# TOP.net
KiCad netlist of a schematic drawn in Altium Designer
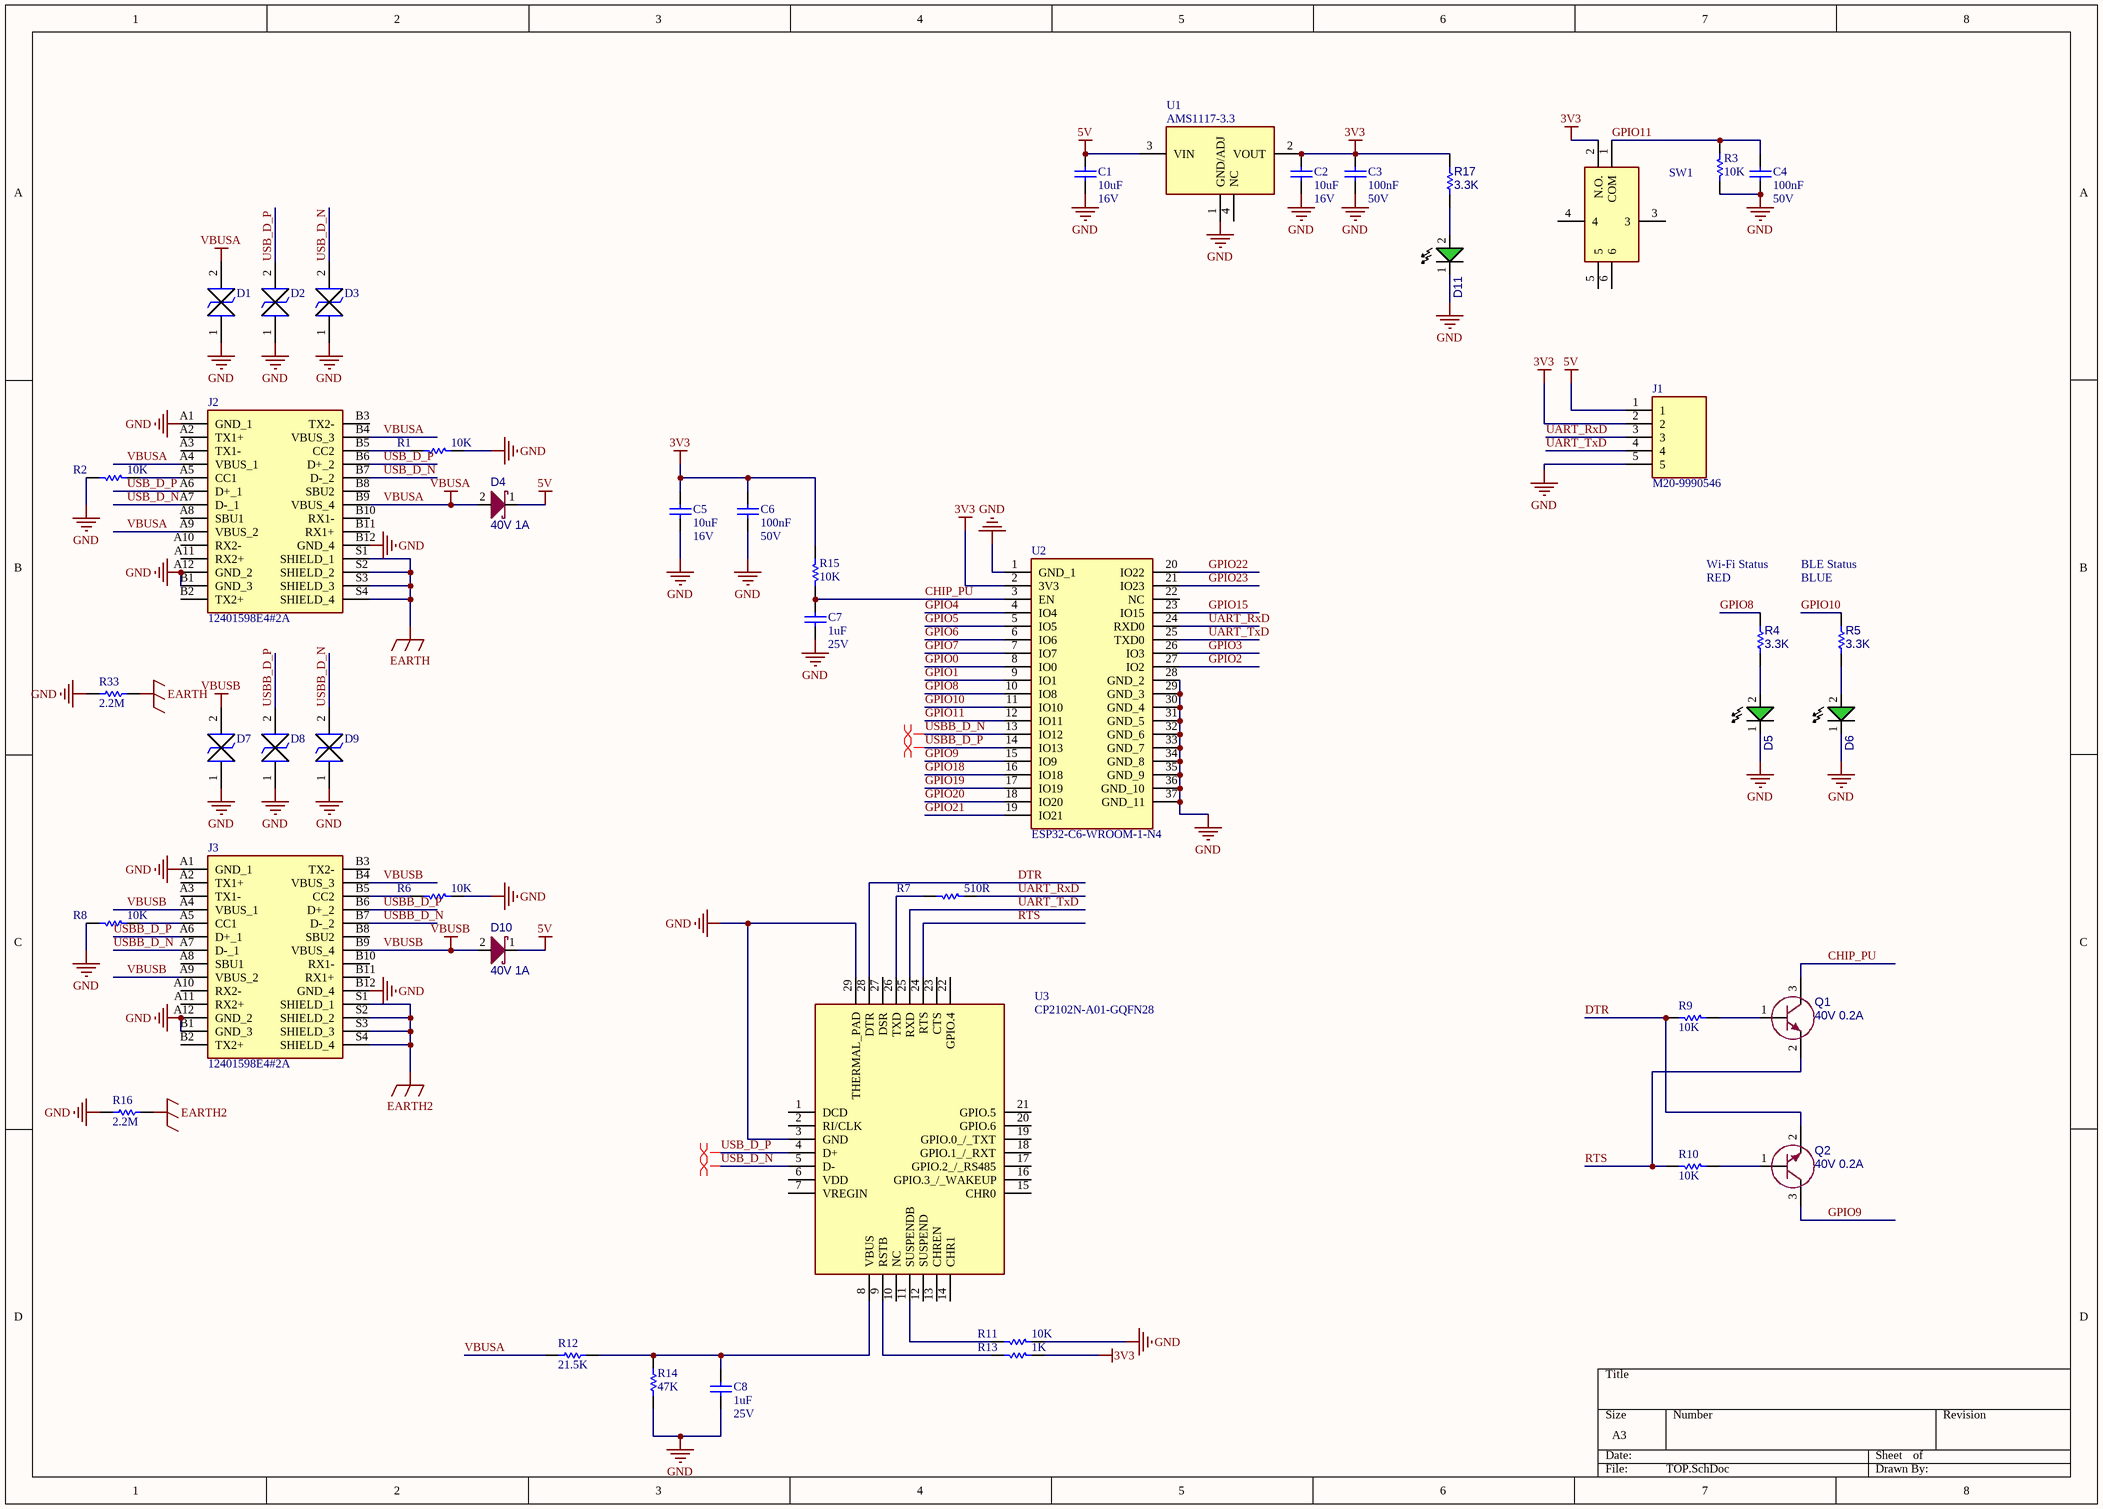
[diagram p0: TOP.SchDoc]

(export (version "E")
  (design (tool "Eeschema 10.0.6"))
  (components
    (comp (ref "C1")
      (value "10uF")
      (footprint "CAP_0805")
      (description "CAP CER 10UF 16VDC %10 X5R SMD")
      (fields
        (field (name "VOLTAGE") "16V")
        (field (name "MANUFACTURER") "Samsung")
        (field (name "MANUFACTURER PART NUMBER") "CL21A106KOQNNNE")
      )
      (libsource (lib "open-components") (part "CAP"))
    )
    (comp (ref "C2")
      (value "10uF")
      (footprint "CAP_0805")
      (description "CAP CER 10UF 16VDC %10 X5R SMD")
      (fields
        (field (name "VOLTAGE") "16V")
        (field (name "MANUFACTURER") "Samsung")
        (field (name "MANUFACTURER PART NUMBER") "CL21A106KOQNNNE")
      )
      (libsource (lib "open-components") (part "CAP"))
    )
    (comp (ref "C3")
      (value "100nF")
      (footprint "CAP_0603")
      (description "CAP CER 100nF 50VDC %10 X7R SMD")
      (fields
        (field (name "VOLTAGE") "50V")
        (field (name "MANUFACTURER") "Samsung")
        (field (name "MANUFACTURER PART NUMBER") "CL10B104KB8NNNL")
      )
      (libsource (lib "open-components") (part "CAP"))
    )
    (comp (ref "C4")
      (value "100nF")
      (footprint "CAP_0603")
      (description "CAP CER 100nF 50VDC %10 X7R SMD")
      (fields
        (field (name "VOLTAGE") "50V")
        (field (name "MANUFACTURER") "Samsung")
        (field (name "MANUFACTURER PART NUMBER") "CL10B104KB8NNNL")
      )
      (libsource (lib "open-components") (part "CAP"))
    )
    (comp (ref "C5")
      (value "10uF")
      (footprint "CAP_0805")
      (description "CAP CER 10UF 16VDC %10 X5R SMD")
      (fields
        (field (name "VOLTAGE") "16V")
        (field (name "MANUFACTURER") "Samsung")
        (field (name "MANUFACTURER PART NUMBER") "CL21A106KOQNNNE")
      )
      (libsource (lib "open-components") (part "CAP"))
    )
    (comp (ref "C6")
      (value "100nF")
      (footprint "CAP_0603")
      (description "CAP CER 100nF 50VDC %10 X7R SMD")
      (fields
        (field (name "VOLTAGE") "50V")
        (field (name "MANUFACTURER") "Samsung")
        (field (name "MANUFACTURER PART NUMBER") "CL10B104KB8NNNL")
      )
      (libsource (lib "open-components") (part "CAP"))
    )
    (comp (ref "C7")
      (value "1uF")
      (footprint "CAP_0603")
      (description "CAP CER 1UF 25VDC %10 X5R SMD")
      (fields
        (field (name "VOLTAGE") "25V")
        (field (name "MANUFACTURER") "Samsung")
        (field (name "MANUFACTURER PART NUMBER") "CL10A105KA8NNNC")
      )
      (libsource (lib "open-components") (part "CAP"))
    )
    (comp (ref "C8")
      (value "1uF")
      (footprint "CAP_0603")
      (description "CAP CER 1UF 25VDC %10 X5R SMD")
      (fields
        (field (name "VOLTAGE") "25V")
        (field (name "MANUFACTURER") "Samsung")
        (field (name "MANUFACTURER PART NUMBER") "CL10A105KA8NNNC")
      )
      (libsource (lib "open-components") (part "CAP"))
    )
    (comp (ref "D1")
      (value "ATV02W5V0B-HF")
      (footprint "SamacSys:SODFL3718X130N")
      (description "TVS Diode (Bi-directional)")
      (fields (field (name "MANUFACTURER") "Comchip Technology"))
      (libsource (lib "SamacSys") (part "ATV02W5V0B-HF"))
    )
    (comp (ref "D2")
      (value "ATV02W5V0B-HF")
      (footprint "SamacSys:SODFL3718X130N")
      (description "TVS Diode (Bi-directional)")
      (fields (field (name "MANUFACTURER") "Comchip Technology"))
      (libsource (lib "SamacSys") (part "ATV02W5V0B-HF"))
    )
    (comp (ref "D3")
      (value "ATV02W5V0B-HF")
      (footprint "SamacSys:SODFL3718X130N")
      (description "TVS Diode (Bi-directional)")
      (fields (field (name "MANUFACTURER") "Comchip Technology"))
      (libsource (lib "SamacSys") (part "ATV02W5V0B-HF"))
    )
    (comp (ref "D4")
      (value "40V 1A")
      (footprint "SOD-123")
      (description "DIODE SCHOTTKY 40V 1A SOD123")
      (fields
        (field (name "MANUFACTURER") "Nexperia USA Inc.")
        (field (name "MANUFACTURER PART NUMBER") "PMEG4010EGWJ")
      )
      (libsource (lib "Semiconductors") (part "PMEG4010EGWJ"))
    )
    (comp (ref "D5")
      (value "PSC-1608U52GC-G4")
      (footprint "LED_0603_GRN")
      (description "LED GREEN WATER CLEAR 0603 SMD")
      (fields (field (name "MANUFACTURER") "HONGLITRONIC"))
      (libsource (lib "Semiconductors") (part "LTST-C190TGKT"))
    )
    (comp (ref "D6")
      (value "PSC-1608U52GC-G4")
      (footprint "LED_0603_GRN")
      (description "LED GREEN WATER CLEAR 0603 SMD")
      (fields (field (name "MANUFACTURER") "HONGLITRONIC"))
      (libsource (lib "Semiconductors") (part "LTST-C190TGKT"))
    )
    (comp (ref "D7")
      (value "ATV02W5V0B-HF")
      (footprint "SamacSys:SODFL3718X130N")
      (description "TVS Diode (Bi-directional)")
      (fields (field (name "MANUFACTURER") "Comchip Technology"))
      (libsource (lib "SamacSys") (part "ATV02W5V0B-HF"))
    )
    (comp (ref "D8")
      (value "ATV02W5V0B-HF")
      (footprint "SamacSys:SODFL3718X130N")
      (description "TVS Diode (Bi-directional)")
      (fields (field (name "MANUFACTURER") "Comchip Technology"))
      (libsource (lib "SamacSys") (part "ATV02W5V0B-HF"))
    )
    (comp (ref "D9")
      (value "ATV02W5V0B-HF")
      (footprint "SamacSys:SODFL3718X130N")
      (description "TVS Diode (Bi-directional)")
      (fields (field (name "MANUFACTURER") "Comchip Technology"))
      (libsource (lib "SamacSys") (part "ATV02W5V0B-HF"))
    )
    (comp (ref "D10")
      (value "40V 1A")
      (footprint "SOD-123")
      (description "DIODE SCHOTTKY 40V 1A SOD123")
      (fields
        (field (name "MANUFACTURER") "Nexperia USA Inc.")
        (field (name "MANUFACTURER PART NUMBER") "PMEG4010EGWJ")
      )
      (libsource (lib "Semiconductors") (part "PMEG4010EGWJ"))
    )
    (comp (ref "D11")
      (value "PSC-1608U52GC-G4")
      (footprint "LED_0603_GRN")
      (description "LED GREEN WATER CLEAR 0603 SMD")
      (fields (field (name "MANUFACTURER") "HONGLITRONIC"))
      (libsource (lib "Semiconductors") (part "LTST-C190TGKT"))
    )
    (comp (ref "J1")
      (value "M20-9990546")
      (footprint "SamacSys:HDRV5W64P0X254_1X5_1270X254X864P")
      (description "Connector")
      (fields (field (name "MANUFACTURER") "Harwin"))
      (libsource (lib "*") (part "M20-9990546"))
    )
    (comp (ref "J2")
      (value "12401598E4#2A")
      (footprint "12401598E42A")
      (description "Connector")
      (fields (field (name "MANUFACTURER") "Amphenol"))
      (libsource (lib "*") (part "12401598E4#2A"))
    )
    (comp (ref "J3")
      (value "12401598E4#2A")
      (footprint "12401598E42A")
      (description "Connector")
      (fields (field (name "MANUFACTURER") "Amphenol"))
      (libsource (lib "*") (part "12401598E4#2A"))
    )
    (comp (ref "Q1")
      (value "40V 0.2A")
      (footprint "SOT23")
      (description "TRANSISTOR NPN 40V 0.2A SOT23-3")
      (fields
        (field (name "MANUFACTURER") "Diodes Incorporated")
        (field (name "MANUFACTURER PART NUMBER") "MMBT3904-7-F")
      )
      (libsource (lib "Semiconductors") (part "MMBT3904-7-F"))
    )
    (comp (ref "Q2")
      (value "40V 0.2A")
      (footprint "SOT23")
      (description "TRANSISTOR NPN 40V 0.2A SOT23-3")
      (fields
        (field (name "MANUFACTURER") "Diodes Incorporated")
        (field (name "MANUFACTURER PART NUMBER") "MMBT3904-7-F")
      )
      (libsource (lib "Semiconductors") (part "MMBT3904-7-F"))
    )
    (comp (ref "R1")
      (value "10K")
      (footprint "RES_0603")
      (description "RES 0603 10k Ohms %1 1/10W 100PPM")
      (fields
        (field (name "MANUFACTURER") "ROYALOHM")
        (field (name "MANUFACTURER PART NUMBER") "0603SAF1002T5E")
      )
      (libsource (lib "open-components") (part "RES"))
    )
    (comp (ref "R2")
      (value "10K")
      (footprint "RES_0603")
      (description "RES 0603 10k Ohms %1 1/10W 100PPM")
      (fields
        (field (name "MANUFACTURER") "ROYALOHM")
        (field (name "MANUFACTURER PART NUMBER") "0603SAF1002T5E")
      )
      (libsource (lib "open-components") (part "RES"))
    )
    (comp (ref "R3")
      (value "10K")
      (footprint "RES_0603")
      (description "RES 0603 10k Ohms %1 1/10W 100PPM")
      (fields
        (field (name "MANUFACTURER") "ROYALOHM")
        (field (name "MANUFACTURER PART NUMBER") "0603SAF1002T5E")
      )
      (libsource (lib "open-components") (part "RES"))
    )
    (comp (ref "R4")
      (value "3.3K")
      (footprint "RES_0603")
      (description "RES.(1608) 0603 3.3K Ohms 1% 1/10W 100PPM SMT")
      (fields
        (field (name "MANUFACTURER") "YAGEO")
        (field (name "MANUFACTURER PART NUMBER") "RC0603FR-073K74L")
      )
      (libsource (lib "Passives") (part "0603SAF3301T5E"))
    )
    (comp (ref "R5")
      (value "3.3K")
      (footprint "RES_0603")
      (description "RES.(1608) 0603 3.3K Ohms 1% 1/10W 100PPM SMT")
      (fields
        (field (name "MANUFACTURER") "YAGEO")
        (field (name "MANUFACTURER PART NUMBER") "RC0603FR-073K74L")
      )
      (libsource (lib "Passives") (part "0603SAF3301T5E"))
    )
    (comp (ref "R6")
      (value "10K")
      (footprint "RES_0603")
      (description "RES 0603 10k Ohms %1 1/10W 100PPM")
      (fields
        (field (name "MANUFACTURER") "ROYALOHM")
        (field (name "MANUFACTURER PART NUMBER") "0603SAF1002T5E")
      )
      (libsource (lib "open-components") (part "RES"))
    )
    (comp (ref "R7")
      (value "510R")
      (footprint "R0603")
      (description "RES.(1608) 0603 510 Ohms 5% 1/10W-S 100PPM")
      (fields
        (field (name "MANUFACTURER") "ROYALOHM")
        (field (name "MANUFACTURER PART NUMBER") "0603SAJ0511T5E")
      )
      (libsource (lib "open-components") (part "RES"))
    )
    (comp (ref "R8")
      (value "10K")
      (footprint "RES_0603")
      (description "RES 0603 10k Ohms %1 1/10W 100PPM")
      (fields
        (field (name "MANUFACTURER") "ROYALOHM")
        (field (name "MANUFACTURER PART NUMBER") "0603SAF1002T5E")
      )
      (libsource (lib "open-components") (part "RES"))
    )
    (comp (ref "R9")
      (value "10K")
      (footprint "RES_0603")
      (description "RES 0603 10k Ohms %1 1/10W 100PPM")
      (fields
        (field (name "MANUFACTURER") "ROYALOHM")
        (field (name "MANUFACTURER PART NUMBER") "0603SAF1002T5E")
      )
      (libsource (lib "open-components") (part "RES"))
    )
    (comp (ref "R10")
      (value "10K")
      (footprint "RES_0603")
      (description "RES 0603 10k Ohms %1 1/10W 100PPM")
      (fields
        (field (name "MANUFACTURER") "ROYALOHM")
        (field (name "MANUFACTURER PART NUMBER") "0603SAF1002T5E")
      )
      (libsource (lib "open-components") (part "RES"))
    )
    (comp (ref "R11")
      (value "10K")
      (footprint "RES_0603")
      (description "RES 0603 10k Ohms %1 1/10W 100PPM")
      (fields
        (field (name "MANUFACTURER") "ROYALOHM")
        (field (name "MANUFACTURER PART NUMBER") "0603SAF1002T5E")
      )
      (libsource (lib "open-components") (part "RES"))
    )
    (comp (ref "R12")
      (value "21.5K")
      (footprint "RES_0603")
      (description "RES.(1608) 0603 21.5K Ohms 1% 1/10W-S 100PPM")
      (fields
        (field (name "MANUFACTURER") "ROYALOHM")
        (field (name "MANUFACTURER PART NUMBER") "0603SAF2152T5E")
      )
      (libsource (lib "open-components") (part "RES"))
    )
    (comp (ref "R13")
      (value "1K")
      (footprint "RES_0603")
      (description "RES 0603 1K Ohms 1% 1/10W-S 100PPM")
      (fields
        (field (name "MANUFACTURER") "ROYALOHM")
        (field (name "MANUFACTURER PART NUMBER") "0603SAF1001T5E")
      )
      (libsource (lib "open-components") (part "RES"))
    )
    (comp (ref "R14")
      (value "47K")
      (footprint "RES_0603")
      (description "RES 0603 47K Ohms 1% 1/10W-S 100PPM")
      (fields
        (field (name "MANUFACTURER") "ROYALOHM")
        (field (name "MANUFACTURER PART NUMBER") "0603SAF4702T5E")
      )
      (libsource (lib "open-components") (part "RES"))
    )
    (comp (ref "R15")
      (value "10K")
      (footprint "RES_0603")
      (description "RES 0603 10k Ohms %1 1/10W 100PPM")
      (fields
        (field (name "MANUFACTURER") "ROYALOHM")
        (field (name "MANUFACTURER PART NUMBER") "0603SAF1002T5E")
      )
      (libsource (lib "open-components") (part "RES"))
    )
    (comp (ref "R16")
      (value "2.2M")
      (footprint "RES_0805")
      (description "RES SMD 2.2M OHM 1% 1/8W 0805")
      (fields
        (field (name "MANUFACTURER") "Yageo")
        (field (name "MANUFACTURER PART NUMBER") "RC0805FR-072M2L")
      )
      (libsource (lib "open-components") (part "RES"))
    )
    (comp (ref "R17")
      (value "3.3K")
      (footprint "RES_0603")
      (description "RES.(1608) 0603 3.3K Ohms 1% 1/10W 100PPM SMT")
      (fields
        (field (name "MANUFACTURER") "YAGEO")
        (field (name "MANUFACTURER PART NUMBER") "RC0603FR-073K74L")
      )
      (libsource (lib "Passives") (part "0603SAF3301T5E"))
    )
    (comp (ref "R33")
      (value "2.2M")
      (footprint "RES_0805")
      (description "RES SMD 2.2M OHM 1% 1/8W 0805")
      (fields
        (field (name "MANUFACTURER") "Yageo")
        (field (name "MANUFACTURER PART NUMBER") "RC0805FR-072M2L")
      )
      (libsource (lib "open-components") (part "RES"))
    )
    (comp (ref "SW1")
      (value "TS32-7-35-BK-B-260-RA-SMT-TR")
      (footprint "TS32735BKB160RAHSMTTR")
      (description "Switch")
      (fields (field (name "MANUFACTURER") "Same Sky"))
      (libsource (lib "*") (part "TS32-7-35-BK-B-260-RA-SMT-TR"))
    )
    (comp (ref "U1")
      (value "AMS1117-3.3")
      (footprint "SamacSys:SOT229P700X180-4N")
      (description "Integrated Circuit")
      (fields (field (name "MANUFACTURER") "Advanced"))
      (libsource (lib "SamacSys") (part "AMS1117-3.3"))
    )
    (comp (ref "U2")
      (value "ESP32-C6-WROOM-1-N4")
      (footprint "SamacSys:ESP32C6WROOM1N4")
      (description "Integrated Circuit")
      (fields (field (name "MANUFACTURER") "Espressif Systems"))
      (libsource (lib "*") (part "ESP32-C6-WROOM-1-N4"))
    )
    (comp (ref "U3")
      (value "CP2102N-A01-GQFN28")
      (footprint "SamacSys:QFN50P500X500X80-29N-D")
      (description "Integrated Circuit")
      (fields (field (name "MANUFACTURER") "Silicon Labs"))
      (libsource (lib "*") (part "CP2102N-A01-GQFN28"))
    )
  )
  (nets
    (net (code "1") (name "/CHIP_PU") (class "Default")
      (node (ref "C7") (pin "1") (pinfunction "1_1") (pintype "passive"))
      (node (ref "Q1") (pin "3") (pinfunction "C_3") (pintype "passive"))
      (node (ref "R15") (pin "1") (pinfunction "1_1") (pintype "passive"))
      (node (ref "U2") (pin "3") (pinfunction "EN_3") (pintype "passive"))
    )
    (net (code "2") (name "/DTR") (class "Default")
      (node (ref "Q2") (pin "2") (pinfunction "E_2") (pintype "passive"))
      (node (ref "R9") (pin "1") (pinfunction "1_1") (pintype "passive"))
      (node (ref "U3") (pin "28") (pinfunction "DTR_28") (pintype "passive"))
    )
    (net (code "3") (name "/GPIO0") (class "Default")
      (node (ref "U2") (pin "8") (pinfunction "IO0_8") (pintype "passive"))
    )
    (net (code "4") (name "/GPIO1") (class "Default")
      (node (ref "U2") (pin "9") (pinfunction "IO1_9") (pintype "passive"))
    )
    (net (code "5") (name "/GPIO2") (class "Default")
      (node (ref "U2") (pin "27") (pinfunction "IO2_27") (pintype "passive"))
    )
    (net (code "6") (name "/GPIO3") (class "Default")
      (node (ref "U2") (pin "26") (pinfunction "IO3_26") (pintype "passive"))
    )
    (net (code "7") (name "/GPIO4") (class "Default")
      (node (ref "U2") (pin "4") (pinfunction "IO4_4") (pintype "passive"))
    )
    (net (code "8") (name "/GPIO5") (class "Default")
      (node (ref "U2") (pin "5") (pinfunction "IO5_5") (pintype "passive"))
    )
    (net (code "9") (name "/GPIO6") (class "Default")
      (node (ref "U2") (pin "6") (pinfunction "IO6_6") (pintype "passive"))
    )
    (net (code "10") (name "/GPIO7") (class "Default")
      (node (ref "U2") (pin "7") (pinfunction "IO7_7") (pintype "passive"))
    )
    (net (code "11") (name "/GPIO8") (class "Default")
      (node (ref "R4") (pin "2") (pinfunction "2_2") (pintype "passive"))
      (node (ref "U2") (pin "10") (pinfunction "IO8_10") (pintype "passive"))
    )
    (net (code "12") (name "/GPIO9") (class "Default")
      (node (ref "Q2") (pin "3") (pinfunction "C_3") (pintype "passive"))
      (node (ref "U2") (pin "15") (pinfunction "IO9_15") (pintype "passive"))
    )
    (net (code "13") (name "/GPIO10") (class "Default")
      (node (ref "R5") (pin "2") (pinfunction "2_2") (pintype "passive"))
      (node (ref "U2") (pin "11") (pinfunction "IO10_11") (pintype "passive"))
    )
    (net (code "14") (name "/GPIO11") (class "Default")
      (node (ref "C4") (pin "1") (pinfunction "1_1") (pintype "passive"))
      (node (ref "R3") (pin "2") (pinfunction "2_2") (pintype "passive"))
      (node (ref "SW1") (pin "1") (pinfunction "COM_1") (pintype "passive"))
      (node (ref "U2") (pin "12") (pinfunction "IO11_12") (pintype "passive"))
    )
    (net (code "15") (name "/GPIO15") (class "Default")
      (node (ref "U2") (pin "23") (pinfunction "IO15_23") (pintype "passive"))
    )
    (net (code "16") (name "/GPIO18") (class "Default")
      (node (ref "U2") (pin "16") (pinfunction "IO18_16") (pintype "passive"))
    )
    (net (code "17") (name "/GPIO19") (class "Default")
      (node (ref "U2") (pin "17") (pinfunction "IO19_17") (pintype "passive"))
    )
    (net (code "18") (name "/GPIO20") (class "Default")
      (node (ref "U2") (pin "18") (pinfunction "IO20_18") (pintype "passive"))
    )
    (net (code "19") (name "/GPIO21") (class "Default")
      (node (ref "U2") (pin "19") (pinfunction "IO21_19") (pintype "passive"))
    )
    (net (code "20") (name "/GPIO22") (class "Default")
      (node (ref "U2") (pin "20") (pinfunction "IO22_20") (pintype "passive"))
    )
    (net (code "21") (name "/GPIO23") (class "Default")
      (node (ref "U2") (pin "21") (pinfunction "IO23_21") (pintype "passive"))
    )
    (net (code "22") (name "/RTS") (class "Default")
      (node (ref "Q1") (pin "2") (pinfunction "E_2") (pintype "passive"))
      (node (ref "R10") (pin "1") (pinfunction "1_1") (pintype "passive"))
      (node (ref "U3") (pin "24") (pinfunction "RTS_24") (pintype "passive"))
    )
    (net (code "23") (name "/UART_RxD") (class "Default")
      (node (ref "J1") (pin "3") (pinfunction "3_3") (pintype "passive"))
      (node (ref "R7") (pin "2") (pinfunction "2_2") (pintype "passive"))
      (node (ref "U2") (pin "24") (pinfunction "RXD0_24") (pintype "passive"))
    )
    (net (code "24") (name "/UART_TxD") (class "Default")
      (node (ref "J1") (pin "4") (pinfunction "4_4") (pintype "passive"))
      (node (ref "U2") (pin "25") (pinfunction "TXD0_25") (pintype "passive"))
      (node (ref "U3") (pin "25") (pinfunction "RXD_25") (pintype "passive"))
    )
    (net (code "25") (name "/USBB_D_N") (class "Default")
      (node (ref "D9") (pin "2") (pinfunction "2_2") (pintype "passive"))
      (node (ref "J3") (pin "A7") (pinfunction "D-_1_A7") (pintype "passive"))
      (node (ref "J3") (pin "B7") (pinfunction "D-_2_B7") (pintype "passive"))
      (node (ref "U2") (pin "13") (pinfunction "IO12_13") (pintype "passive"))
    )
    (net (code "26") (name "/USBB_D_P") (class "Default")
      (node (ref "D8") (pin "2") (pinfunction "2_2") (pintype "passive"))
      (node (ref "J3") (pin "A6") (pinfunction "D+_1_A6") (pintype "passive"))
      (node (ref "J3") (pin "B6") (pinfunction "D+_2_B6") (pintype "passive"))
      (node (ref "U2") (pin "14") (pinfunction "IO13_14") (pintype "passive"))
    )
    (net (code "27") (name "/USB_D_N") (class "Default")
      (node (ref "D3") (pin "2") (pinfunction "2_2") (pintype "passive"))
      (node (ref "J2") (pin "A7") (pinfunction "D-_1_A7") (pintype "passive"))
      (node (ref "J2") (pin "B7") (pinfunction "D-_2_B7") (pintype "passive"))
      (node (ref "U3") (pin "5") (pinfunction "D-_5") (pintype "passive"))
    )
    (net (code "28") (name "/USB_D_P") (class "Default")
      (node (ref "D2") (pin "2") (pinfunction "2_2") (pintype "passive"))
      (node (ref "J2") (pin "A6") (pinfunction "D+_1_A6") (pintype "passive"))
      (node (ref "J2") (pin "B6") (pinfunction "D+_2_B6") (pintype "passive"))
      (node (ref "U3") (pin "4") (pinfunction "D+_4") (pintype "passive"))
    )
    (net (code "29") (name "3V3") (class "Default")
      (node (ref "C2") (pin "1") (pinfunction "1_1") (pintype "passive"))
      (node (ref "C3") (pin "1") (pinfunction "1_1") (pintype "passive"))
      (node (ref "C5") (pin "1") (pinfunction "1_1") (pintype "passive"))
      (node (ref "C6") (pin "1") (pinfunction "1_1") (pintype "passive"))
      (node (ref "J1") (pin "2") (pinfunction "2_2") (pintype "passive"))
      (node (ref "R13") (pin "2") (pinfunction "2_2") (pintype "passive"))
      (node (ref "R15") (pin "2") (pinfunction "2_2") (pintype "passive"))
      (node (ref "R17") (pin "2") (pinfunction "2_2") (pintype "passive"))
      (node (ref "SW1") (pin "2") (pinfunction "N.O._2") (pintype "passive"))
      (node (ref "U1") (pin "2") (pinfunction "VOUT_2") (pintype "passive"))
      (node (ref "U2") (pin "2") (pinfunction "3V3_2") (pintype "passive"))
    )
    (net (code "30") (name "5V") (class "Default")
      (node (ref "C1") (pin "1") (pinfunction "1_1") (pintype "passive"))
      (node (ref "D10") (pin "1") (pinfunction "1_1") (pintype "passive"))
      (node (ref "D4") (pin "1") (pinfunction "1_1") (pintype "passive"))
      (node (ref "J1") (pin "1") (pinfunction "1_1") (pintype "passive"))
      (node (ref "U1") (pin "3") (pinfunction "VIN_3") (pintype "passive"))
    )
    (net (code "31") (name "EARTH") (class "Default")
      (node (ref "J2") (pin "S1") (pinfunction "SHIELD_1_S1") (pintype "passive"))
      (node (ref "J2") (pin "S2") (pinfunction "SHIELD_2_S2") (pintype "passive"))
      (node (ref "J2") (pin "S3") (pinfunction "SHIELD_3_S3") (pintype "passive"))
      (node (ref "J2") (pin "S4") (pinfunction "SHIELD_4_S4") (pintype "passive"))
      (node (ref "R33") (pin "2") (pinfunction "2_2") (pintype "passive"))
    )
    (net (code "32") (name "EARTH2") (class "Default")
      (node (ref "J3") (pin "S1") (pinfunction "SHIELD_1_S1") (pintype "passive"))
      (node (ref "J3") (pin "S2") (pinfunction "SHIELD_2_S2") (pintype "passive"))
      (node (ref "J3") (pin "S3") (pinfunction "SHIELD_3_S3") (pintype "passive"))
      (node (ref "J3") (pin "S4") (pinfunction "SHIELD_4_S4") (pintype "passive"))
      (node (ref "R16") (pin "2") (pinfunction "2_2") (pintype "passive"))
    )
    (net (code "33") (name "GND") (class "Default")
      (node (ref "C1") (pin "2") (pinfunction "2_2") (pintype "passive"))
      (node (ref "C2") (pin "2") (pinfunction "2_2") (pintype "passive"))
      (node (ref "C3") (pin "2") (pinfunction "2_2") (pintype "passive"))
      (node (ref "C4") (pin "2") (pinfunction "2_2") (pintype "passive"))
      (node (ref "C5") (pin "2") (pinfunction "2_2") (pintype "passive"))
      (node (ref "C6") (pin "2") (pinfunction "2_2") (pintype "passive"))
      (node (ref "C7") (pin "2") (pinfunction "2_2") (pintype "passive"))
      (node (ref "C8") (pin "2") (pinfunction "2_2") (pintype "passive"))
      (node (ref "D1") (pin "1") (pinfunction "1_1") (pintype "passive"))
      (node (ref "D11") (pin "1") (pinfunction "1_1") (pintype "passive"))
      (node (ref "D2") (pin "1") (pinfunction "1_1") (pintype "passive"))
      (node (ref "D3") (pin "1") (pinfunction "1_1") (pintype "passive"))
      (node (ref "D5") (pin "1") (pinfunction "1_1") (pintype "passive"))
      (node (ref "D6") (pin "1") (pinfunction "1_1") (pintype "passive"))
      (node (ref "D7") (pin "1") (pinfunction "1_1") (pintype "passive"))
      (node (ref "D8") (pin "1") (pinfunction "1_1") (pintype "passive"))
      (node (ref "D9") (pin "1") (pinfunction "1_1") (pintype "passive"))
      (node (ref "J1") (pin "5") (pinfunction "5_5") (pintype "passive"))
      (node (ref "J2") (pin "A1") (pinfunction "GND_1_A1") (pintype "passive"))
      (node (ref "J2") (pin "A12") (pinfunction "GND_2_A12") (pintype "passive"))
      (node (ref "J2") (pin "B1") (pinfunction "GND_3_B1") (pintype "passive"))
      (node (ref "J2") (pin "B12") (pinfunction "GND_4_B12") (pintype "passive"))
      (node (ref "J3") (pin "A1") (pinfunction "GND_1_A1") (pintype "passive"))
      (node (ref "J3") (pin "A12") (pinfunction "GND_2_A12") (pintype "passive"))
      (node (ref "J3") (pin "B1") (pinfunction "GND_3_B1") (pintype "passive"))
      (node (ref "J3") (pin "B12") (pinfunction "GND_4_B12") (pintype "passive"))
      (node (ref "R1") (pin "2") (pinfunction "2_2") (pintype "passive"))
      (node (ref "R11") (pin "2") (pinfunction "2_2") (pintype "passive"))
      (node (ref "R14") (pin "2") (pinfunction "2_2") (pintype "passive"))
      (node (ref "R16") (pin "1") (pinfunction "1_1") (pintype "passive"))
      (node (ref "R2") (pin "1") (pinfunction "1_1") (pintype "passive"))
      (node (ref "R3") (pin "1") (pinfunction "1_1") (pintype "passive"))
      (node (ref "R33") (pin "1") (pinfunction "1_1") (pintype "passive"))
      (node (ref "R6") (pin "2") (pinfunction "2_2") (pintype "passive"))
      (node (ref "R8") (pin "1") (pinfunction "1_1") (pintype "passive"))
      (node (ref "U1") (pin "1") (pinfunction "GND/ADJ_1") (pintype "passive"))
      (node (ref "U2") (pin "1") (pinfunction "GND_1_1") (pintype "passive"))
      (node (ref "U2") (pin "28") (pinfunction "GND_2_28") (pintype "passive"))
      (node (ref "U2") (pin "29") (pinfunction "GND_3_29") (pintype "passive"))
      (node (ref "U2") (pin "30") (pinfunction "GND_4_30") (pintype "passive"))
      (node (ref "U2") (pin "31") (pinfunction "GND_5_31") (pintype "passive"))
      (node (ref "U2") (pin "32") (pinfunction "GND_6_32") (pintype "passive"))
      (node (ref "U2") (pin "33") (pinfunction "GND_7_33") (pintype "passive"))
      (node (ref "U2") (pin "34") (pinfunction "GND_8_34") (pintype "passive"))
      (node (ref "U2") (pin "35") (pinfunction "GND_9_35") (pintype "passive"))
      (node (ref "U2") (pin "36") (pinfunction "GND_10_36") (pintype "passive"))
      (node (ref "U2") (pin "37") (pinfunction "GND_11_37") (pintype "passive"))
      (node (ref "U3") (pin "29") (pinfunction "THERMAL_PAD_29") (pintype "passive"))
      (node (ref "U3") (pin "3") (pinfunction "GND_3") (pintype "passive"))
    )
    (net (code "34") (name "Net-(D5-Pad2)") (class "Default")
      (node (ref "D5") (pin "2") (pinfunction "2_2") (pintype "passive"))
      (node (ref "R4") (pin "1") (pinfunction "1_1") (pintype "passive"))
    )
    (net (code "35") (name "Net-(D6-Pad2)") (class "Default")
      (node (ref "D6") (pin "2") (pinfunction "2_2") (pintype "passive"))
      (node (ref "R5") (pin "1") (pinfunction "1_1") (pintype "passive"))
    )
    (net (code "36") (name "Net-(D11-Pad2)") (class "Default")
      (node (ref "D11") (pin "2") (pinfunction "2_2") (pintype "passive"))
      (node (ref "R17") (pin "1") (pinfunction "1_1") (pintype "passive"))
    )
    (net (code "37") (name "Net-(J2-CC1)") (class "Default")
      (node (ref "J2") (pin "A5") (pinfunction "CC1_A5") (pintype "passive"))
      (node (ref "R2") (pin "2") (pinfunction "2_2") (pintype "passive"))
    )
    (net (code "38") (name "Net-(J2-CC2)") (class "Default")
      (node (ref "J2") (pin "B5") (pinfunction "CC2_B5") (pintype "passive"))
      (node (ref "R1") (pin "1") (pinfunction "1_1") (pintype "passive"))
    )
    (net (code "39") (name "Net-(J3-CC1)") (class "Default")
      (node (ref "J3") (pin "A5") (pinfunction "CC1_A5") (pintype "passive"))
      (node (ref "R8") (pin "2") (pinfunction "2_2") (pintype "passive"))
    )
    (net (code "40") (name "Net-(J3-CC2)") (class "Default")
      (node (ref "J3") (pin "B5") (pinfunction "CC2_B5") (pintype "passive"))
      (node (ref "R6") (pin "1") (pinfunction "1_1") (pintype "passive"))
    )
    (net (code "41") (name "Net-(Q1-B)") (class "Default")
      (node (ref "Q1") (pin "1") (pinfunction "B_1") (pintype "passive"))
      (node (ref "R9") (pin "2") (pinfunction "2_2") (pintype "passive"))
    )
    (net (code "42") (name "Net-(Q2-B)") (class "Default")
      (node (ref "Q2") (pin "1") (pinfunction "B_1") (pintype "passive"))
      (node (ref "R10") (pin "2") (pinfunction "2_2") (pintype "passive"))
    )
    (net (code "43") (name "Net-(U3-RSTB)") (class "Default")
      (node (ref "R13") (pin "1") (pinfunction "1_1") (pintype "passive"))
      (node (ref "U3") (pin "9") (pinfunction "RSTB_9") (pintype "passive"))
    )
    (net (code "44") (name "Net-(U3-SUSPENDB)") (class "Default")
      (node (ref "R11") (pin "1") (pinfunction "1_1") (pintype "passive"))
      (node (ref "U3") (pin "11") (pinfunction "SUSPENDB_11") (pintype "passive"))
    )
    (net (code "45") (name "Net-(U3-TXD)") (class "Default")
      (node (ref "R7") (pin "1") (pinfunction "1_1") (pintype "passive"))
      (node (ref "U3") (pin "26") (pinfunction "TXD_26") (pintype "passive"))
    )
    (net (code "46") (name "Net-(U3-VBUS)") (class "Default")
      (node (ref "C8") (pin "1") (pinfunction "1_1") (pintype "passive"))
      (node (ref "R12") (pin "2") (pinfunction "2_2") (pintype "passive"))
      (node (ref "R14") (pin "1") (pinfunction "1_1") (pintype "passive"))
      (node (ref "U3") (pin "8") (pinfunction "VBUS_8") (pintype "passive"))
    )
    (net (code "47") (name "VBUSA") (class "Default")
      (node (ref "D1") (pin "2") (pinfunction "2_2") (pintype "passive"))
      (node (ref "D4") (pin "2") (pinfunction "2_2") (pintype "passive"))
      (node (ref "J2") (pin "A4") (pinfunction "VBUS_1_A4") (pintype "passive"))
      (node (ref "J2") (pin "A9") (pinfunction "VBUS_2_A9") (pintype "passive"))
      (node (ref "J2") (pin "B4") (pinfunction "VBUS_3_B4") (pintype "passive"))
      (node (ref "J2") (pin "B9") (pinfunction "VBUS_4_B9") (pintype "passive"))
      (node (ref "R12") (pin "1") (pinfunction "1_1") (pintype "passive"))
    )
    (net (code "48") (name "VBUSB") (class "Default")
      (node (ref "D10") (pin "2") (pinfunction "2_2") (pintype "passive"))
      (node (ref "D7") (pin "2") (pinfunction "2_2") (pintype "passive"))
      (node (ref "J3") (pin "A4") (pinfunction "VBUS_1_A4") (pintype "passive"))
      (node (ref "J3") (pin "A9") (pinfunction "VBUS_2_A9") (pintype "passive"))
      (node (ref "J3") (pin "B4") (pinfunction "VBUS_3_B4") (pintype "passive"))
      (node (ref "J3") (pin "B9") (pinfunction "VBUS_4_B9") (pintype "passive"))
    )
    (net (code "49") (name "unconnected-(J2-RX1+-PadB11)") (class "Default")
      (node (ref "J2") (pin "B11") (pinfunction "RX1+_B11") (pintype "passive"))
    )
    (net (code "50") (name "unconnected-(J2-RX1--PadB10)") (class "Default")
      (node (ref "J2") (pin "B10") (pinfunction "RX1-_B10") (pintype "passive"))
    )
    (net (code "51") (name "unconnected-(J2-RX2+-PadA11)") (class "Default")
      (node (ref "J2") (pin "A11") (pinfunction "RX2+_A11") (pintype "passive"))
    )
    (net (code "52") (name "unconnected-(J2-RX2--PadA10)") (class "Default")
      (node (ref "J2") (pin "A10") (pinfunction "RX2-_A10") (pintype "passive"))
    )
    (net (code "53") (name "unconnected-(J2-SBU1-PadA8)") (class "Default")
      (node (ref "J2") (pin "A8") (pinfunction "SBU1_A8") (pintype "passive"))
    )
    (net (code "54") (name "unconnected-(J2-SBU2-PadB8)") (class "Default")
      (node (ref "J2") (pin "B8") (pinfunction "SBU2_B8") (pintype "passive"))
    )
    (net (code "55") (name "unconnected-(J2-TX1+-PadA2)") (class "Default")
      (node (ref "J2") (pin "A2") (pinfunction "TX1+_A2") (pintype "passive"))
    )
    (net (code "56") (name "unconnected-(J2-TX1--PadA3)") (class "Default")
      (node (ref "J2") (pin "A3") (pinfunction "TX1-_A3") (pintype "passive"))
    )
    (net (code "57") (name "unconnected-(J2-TX2+-PadB2)") (class "Default")
      (node (ref "J2") (pin "B2") (pinfunction "TX2+_B2") (pintype "passive"))
    )
    (net (code "58") (name "unconnected-(J2-TX2--PadB3)") (class "Default")
      (node (ref "J2") (pin "B3") (pinfunction "TX2-_B3") (pintype "passive"))
    )
    (net (code "59") (name "unconnected-(J3-RX1+-PadB11)") (class "Default")
      (node (ref "J3") (pin "B11") (pinfunction "RX1+_B11") (pintype "passive"))
    )
    (net (code "60") (name "unconnected-(J3-RX1--PadB10)") (class "Default")
      (node (ref "J3") (pin "B10") (pinfunction "RX1-_B10") (pintype "passive"))
    )
    (net (code "61") (name "unconnected-(J3-RX2+-PadA11)") (class "Default")
      (node (ref "J3") (pin "A11") (pinfunction "RX2+_A11") (pintype "passive"))
    )
    (net (code "62") (name "unconnected-(J3-RX2--PadA10)") (class "Default")
      (node (ref "J3") (pin "A10") (pinfunction "RX2-_A10") (pintype "passive"))
    )
    (net (code "63") (name "unconnected-(J3-SBU1-PadA8)") (class "Default")
      (node (ref "J3") (pin "A8") (pinfunction "SBU1_A8") (pintype "passive"))
    )
    (net (code "64") (name "unconnected-(J3-SBU2-PadB8)") (class "Default")
      (node (ref "J3") (pin "B8") (pinfunction "SBU2_B8") (pintype "passive"))
    )
    (net (code "65") (name "unconnected-(J3-TX1+-PadA2)") (class "Default")
      (node (ref "J3") (pin "A2") (pinfunction "TX1+_A2") (pintype "passive"))
    )
    (net (code "66") (name "unconnected-(J3-TX1--PadA3)") (class "Default")
      (node (ref "J3") (pin "A3") (pinfunction "TX1-_A3") (pintype "passive"))
    )
    (net (code "67") (name "unconnected-(J3-TX2+-PadB2)") (class "Default")
      (node (ref "J3") (pin "B2") (pinfunction "TX2+_B2") (pintype "passive"))
    )
    (net (code "68") (name "unconnected-(J3-TX2--PadB3)") (class "Default")
      (node (ref "J3") (pin "B3") (pinfunction "TX2-_B3") (pintype "passive"))
    )
    (net (code "69") (name "unconnected-(SW1-Pad3)") (class "Default")
      (node (ref "SW1") (pin "3") (pinfunction "3_3") (pintype "passive"))
    )
    (net (code "70") (name "unconnected-(SW1-Pad4)") (class "Default")
      (node (ref "SW1") (pin "4") (pinfunction "4_4") (pintype "passive"))
    )
    (net (code "71") (name "unconnected-(SW1-Pad5)") (class "Default")
      (node (ref "SW1") (pin "5") (pinfunction "5_5") (pintype "passive"))
    )
    (net (code "72") (name "unconnected-(SW1-Pad6)") (class "Default")
      (node (ref "SW1") (pin "6") (pinfunction "6_6") (pintype "passive"))
    )
    (net (code "73") (name "unconnected-(U1-NC-Pad4)") (class "Default")
      (node (ref "U1") (pin "4") (pinfunction "NC_4") (pintype "passive"))
    )
    (net (code "74") (name "unconnected-(U2-NC-Pad22)") (class "Default")
      (node (ref "U2") (pin "22") (pinfunction "NC_22") (pintype "passive"))
    )
    (net (code "75") (name "unconnected-(U3-CHR0-Pad15)") (class "Default")
      (node (ref "U3") (pin "15") (pinfunction "CHR0_15") (pintype "passive"))
    )
    (net (code "76") (name "unconnected-(U3-CHR1-Pad14)") (class "Default")
      (node (ref "U3") (pin "14") (pinfunction "CHR1_14") (pintype "passive"))
    )
    (net (code "77") (name "unconnected-(U3-CHREN-Pad13)") (class "Default")
      (node (ref "U3") (pin "13") (pinfunction "CHREN_13") (pintype "passive"))
    )
    (net (code "78") (name "unconnected-(U3-CTS-Pad23)") (class "Default")
      (node (ref "U3") (pin "23") (pinfunction "CTS_23") (pintype "passive"))
    )
    (net (code "79") (name "unconnected-(U3-DCD-Pad1)") (class "Default")
      (node (ref "U3") (pin "1") (pinfunction "DCD_1") (pintype "passive"))
    )
    (net (code "80") (name "unconnected-(U3-DSR-Pad27)") (class "Default")
      (node (ref "U3") (pin "27") (pinfunction "DSR_27") (pintype "passive"))
    )
    (net (code "81") (name "unconnected-(U3-GPIO.0_{slash}_TXT-Pad19)") (class "Default")
      (node (ref "U3") (pin "19") (pinfunction "GPIO.0_/_TXT_19") (pintype "passive"))
    )
    (net (code "82") (name "unconnected-(U3-GPIO.1_{slash}_RXT-Pad18)") (class "Default")
      (node (ref "U3") (pin "18") (pinfunction "GPIO.1_/_RXT_18") (pintype "passive"))
    )
    (net (code "83") (name "unconnected-(U3-GPIO.2_{slash}_RS485-Pad17)") (class "Default")
      (node (ref "U3") (pin "17") (pinfunction "GPIO.2_/_RS485_17") (pintype "passive"))
    )
    (net (code "84") (name "unconnected-(U3-GPIO.3_{slash}_WAKEUP-Pad16)") (class "Default")
      (node (ref "U3") (pin "16") (pinfunction "GPIO.3_/_WAKEUP_16") (pintype "passive"))
    )
    (net (code "85") (name "unconnected-(U3-GPIO.4-Pad22)") (class "Default")
      (node (ref "U3") (pin "22") (pinfunction "GPIO.4_22") (pintype "passive"))
    )
    (net (code "86") (name "unconnected-(U3-GPIO.5-Pad21)") (class "Default")
      (node (ref "U3") (pin "21") (pinfunction "GPIO.5_21") (pintype "passive"))
    )
    (net (code "87") (name "unconnected-(U3-GPIO.6-Pad20)") (class "Default")
      (node (ref "U3") (pin "20") (pinfunction "GPIO.6_20") (pintype "passive"))
    )
    (net (code "88") (name "unconnected-(U3-NC-Pad10)") (class "Default")
      (node (ref "U3") (pin "10") (pinfunction "NC_10") (pintype "passive"))
    )
    (net (code "89") (name "unconnected-(U3-RI{slash}CLK-Pad2)") (class "Default")
      (node (ref "U3") (pin "2") (pinfunction "RI/CLK_2") (pintype "passive"))
    )
    (net (code "90") (name "unconnected-(U3-SUSPEND-Pad12)") (class "Default")
      (node (ref "U3") (pin "12") (pinfunction "SUSPEND_12") (pintype "passive"))
    )
    (net (code "91") (name "unconnected-(U3-VDD-Pad6)") (class "Default")
      (node (ref "U3") (pin "6") (pinfunction "VDD_6") (pintype "passive"))
    )
    (net (code "92") (name "unconnected-(U3-VREGIN-Pad7)") (class "Default")
      (node (ref "U3") (pin "7") (pinfunction "VREGIN_7") (pintype "passive"))
    )
  )
)
